# Schematic.net
KiCad netlist of a schematic drawn in EAGLE
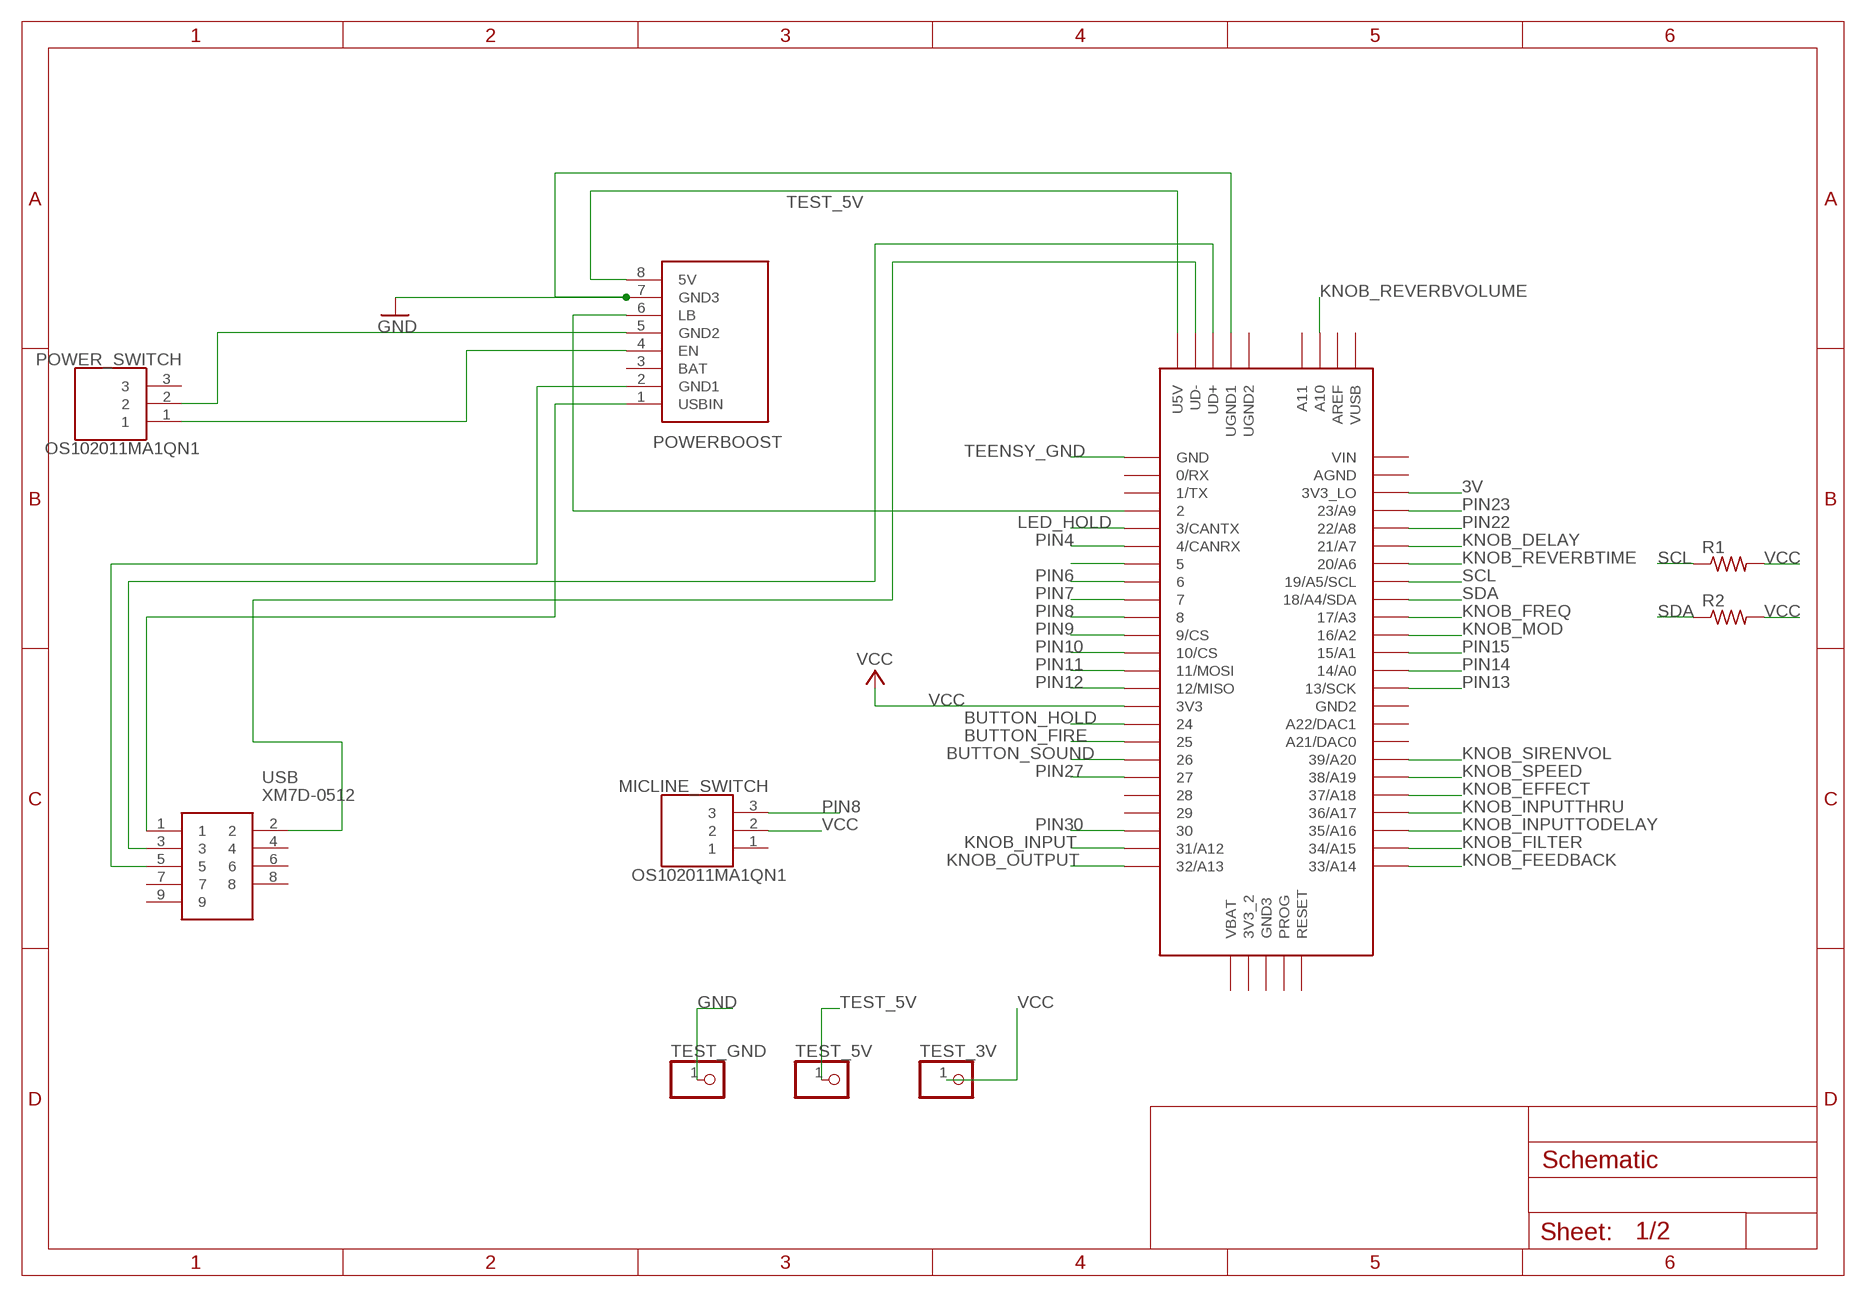
[diagram p0: schematic, sheet 1, part 1 of 2]
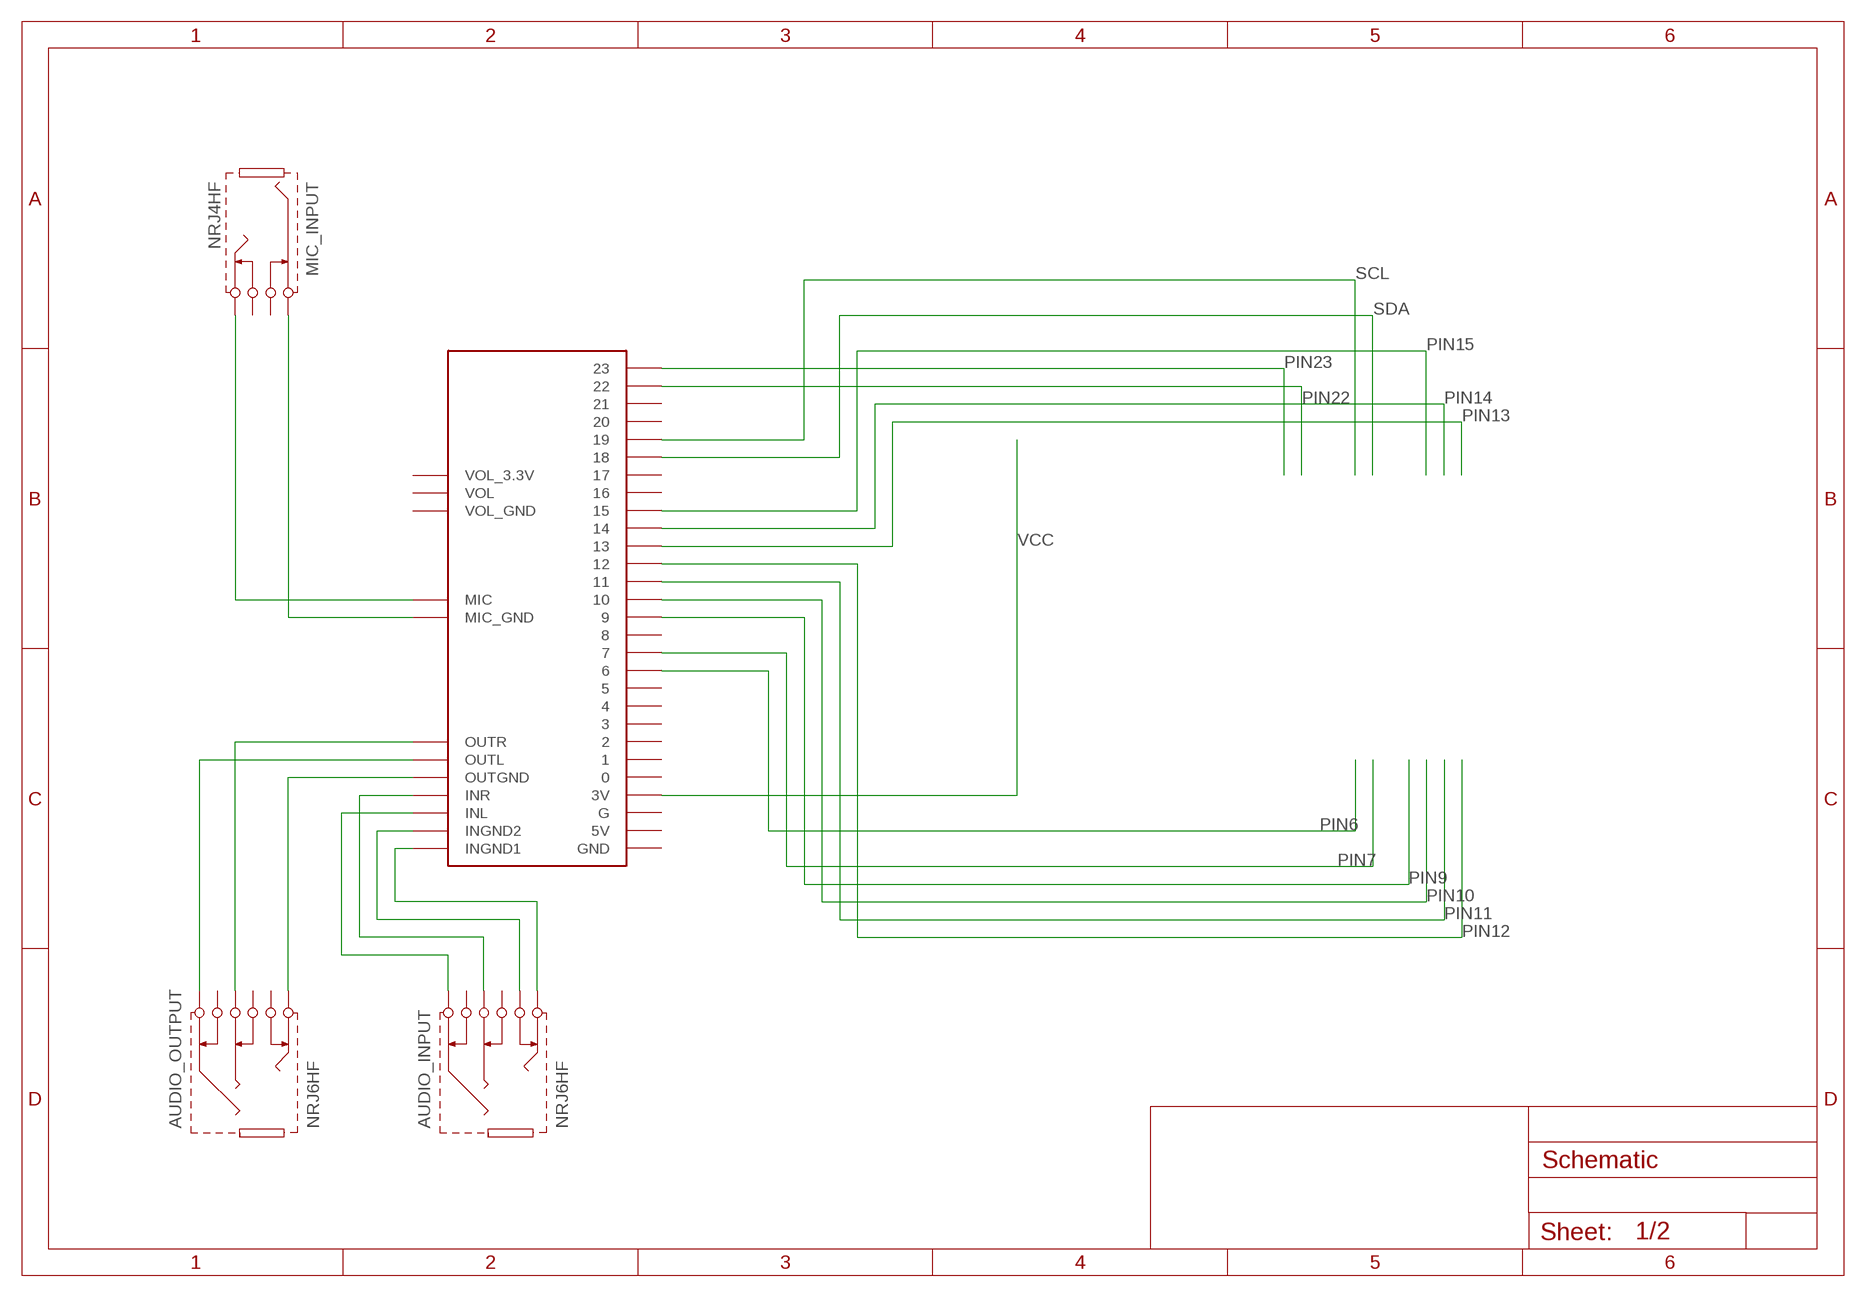
[diagram p1: schematic, sheet 1, part 2 of 2]
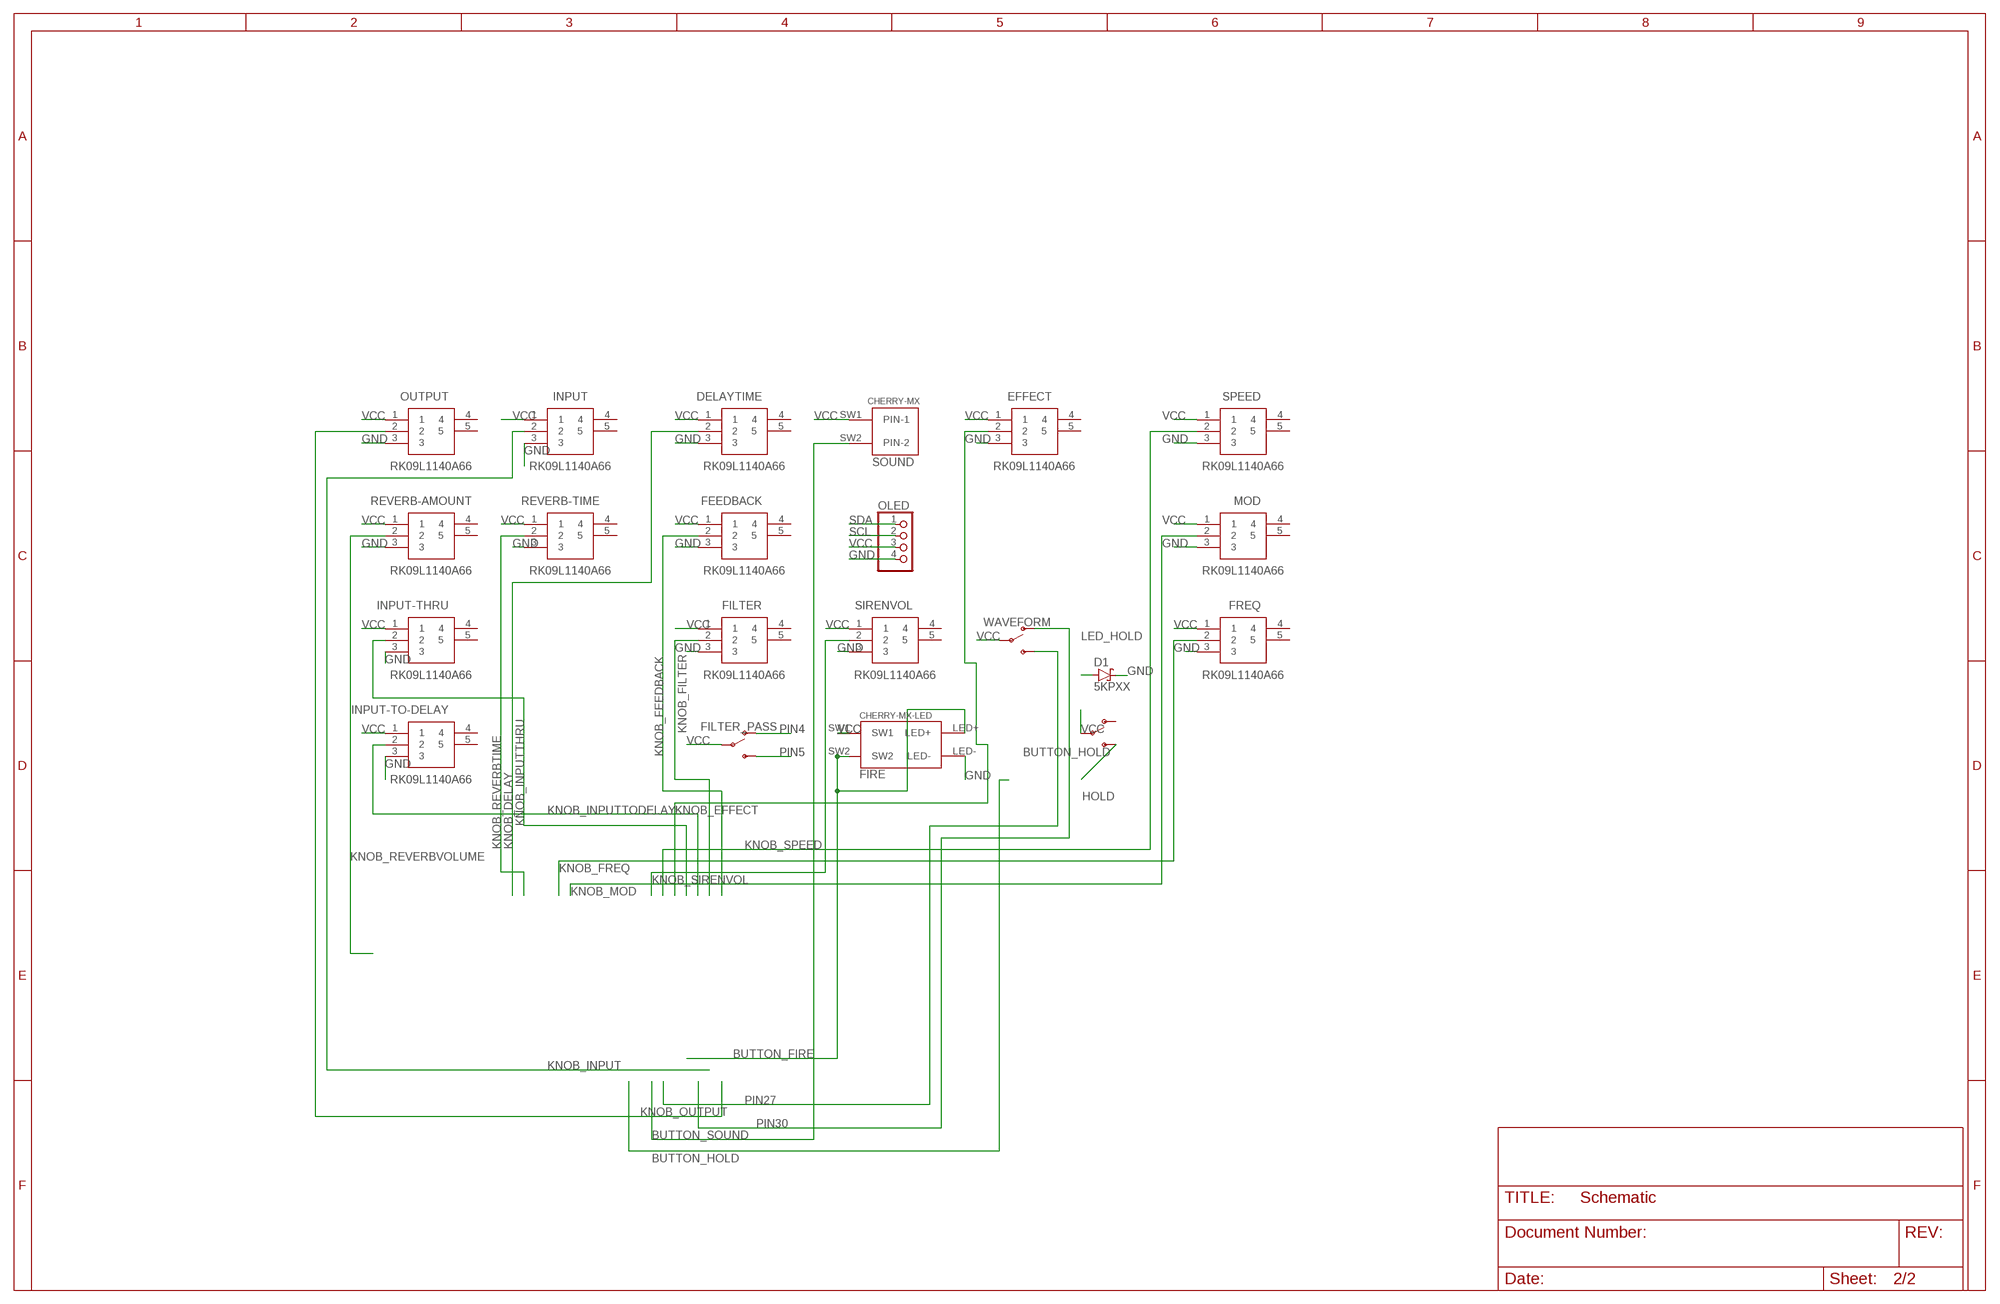
[diagram p2: schematic, sheet 2]

(export (version "E")
  (design (tool "Eeschema 10.0.6"))
  (components
    (comp (ref "D1")
      (value "5KPXX")
      (footprint "eagle-import:P6T15")
      (libsource (lib "eagle-import") (part "5KPXX"))
    )
    (comp (ref "DELAYTIME")
      (value "RK09L1140A66")
      (footprint "eagle-import:RK09L1140A66")
      (fields (field (name "MOUSER_PART_NUMBER") "688-RK09L1140A66"))
      (libsource (lib "eagle-import") (part "RK09L1140A66"))
    )
    (comp (ref "EFFECT")
      (value "RK09L1140A66")
      (footprint "eagle-import:RK09L1140A66")
      (fields (field (name "MOUSER_PART_NUMBER") "688-RK09L1140A66"))
      (libsource (lib "eagle-import") (part "RK09L1140A66"))
    )
    (comp (ref "FEEDBACK")
      (value "RK09L1140A66")
      (footprint "eagle-import:RK09L1140A66")
      (fields (field (name "MOUSER_PART_NUMBER") "688-RK09L1140A66"))
      (libsource (lib "eagle-import") (part "RK09L1140A66"))
    )
    (comp (ref "FILTER")
      (value "RK09L1140A66")
      (footprint "eagle-import:RK09L1140A66")
      (fields (field (name "MOUSER_PART_NUMBER") "688-RK09L1140A66"))
      (libsource (lib "eagle-import") (part "RK09L1140A66"))
    )
    (comp (ref "FILTER_PASS")
      (value "SWITCH-SPDT-PTH-11.6X4.0MM-LOCK")
      (footprint "eagle-import:SWITCH_SPDT_PTH_11.6X4.0MM_LOCK")
      (libsource (lib "eagle-import") (part "SWITCH-SPDT-PTH-11.6X4.0MM-LOCK"))
    )
    (comp (ref "FIRE")
      (value "CHERRY-MX-LED")
      (footprint "eagle-import:CHERRY-MX-LED")
      (libsource (lib "eagle-import") (part "CHERRY-MX-LED"))
    )
    (comp (ref "FREQ")
      (value "RK09L1140A66")
      (footprint "eagle-import:RK09L1140A66")
      (fields (field (name "MOUSER_PART_NUMBER") "688-RK09L1140A66"))
      (libsource (lib "eagle-import") (part "RK09L1140A66"))
    )
    (comp (ref "HOLD")
      (value "SWITCH-SPDT-PTH-11.6X4.0MM-LOCK")
      (footprint "eagle-import:SWITCH_SPDT_PTH_11.6X4.0MM_LOCK")
      (libsource (lib "eagle-import") (part "SWITCH-SPDT-PTH-11.6X4.0MM-LOCK"))
    )
    (comp (ref "INPUT")
      (value "RK09L1140A66")
      (footprint "eagle-import:RK09L1140A66")
      (fields (field (name "MOUSER_PART_NUMBER") "688-RK09L1140A66"))
      (libsource (lib "eagle-import") (part "RK09L1140A66"))
    )
    (comp (ref "INPUT-THRU")
      (value "RK09L1140A66")
      (footprint "eagle-import:RK09L1140A66")
      (fields (field (name "MOUSER_PART_NUMBER") "688-RK09L1140A66"))
      (libsource (lib "eagle-import") (part "RK09L1140A66"))
    )
    (comp (ref "INPUT-TO-DELAY")
      (value "RK09L1140A66")
      (footprint "eagle-import:RK09L1140A66")
      (fields (field (name "MOUSER_PART_NUMBER") "688-RK09L1140A66"))
      (libsource (lib "eagle-import") (part "RK09L1140A66"))
    )
    (comp (ref "MOD")
      (value "RK09L1140A66")
      (footprint "eagle-import:RK09L1140A66")
      (fields (field (name "MOUSER_PART_NUMBER") "688-RK09L1140A66"))
      (libsource (lib "eagle-import") (part "RK09L1140A66"))
    )
    (comp (ref "OLED")
      (value "PINHD-1X4")
      (footprint "eagle-import:1X04")
      (libsource (lib "eagle-import") (part "PINHD-1X4"))
    )
    (comp (ref "OUTPUT")
      (value "RK09L1140A66")
      (footprint "eagle-import:RK09L1140A66")
      (fields (field (name "MOUSER_PART_NUMBER") "688-RK09L1140A66"))
      (libsource (lib "eagle-import") (part "RK09L1140A66"))
    )
    (comp (ref "REVERB-AMOUNT")
      (value "RK09L1140A66")
      (footprint "eagle-import:RK09L1140A66")
      (fields (field (name "MOUSER_PART_NUMBER") "688-RK09L1140A66"))
      (libsource (lib "eagle-import") (part "RK09L1140A66"))
    )
    (comp (ref "REVERB-TIME")
      (value "RK09L1140A66")
      (footprint "eagle-import:RK09L1140A66")
      (fields (field (name "MOUSER_PART_NUMBER") "688-RK09L1140A66"))
      (libsource (lib "eagle-import") (part "RK09L1140A66"))
    )
    (comp (ref "SIRENVOL")
      (value "RK09L1140A66")
      (footprint "eagle-import:RK09L1140A66")
      (fields (field (name "MOUSER_PART_NUMBER") "688-RK09L1140A66"))
      (libsource (lib "eagle-import") (part "RK09L1140A66"))
    )
    (comp (ref "SOUND")
      (value "CHERRY-MX")
      (footprint "eagle-import:CHERRY-MX")
      (libsource (lib "eagle-import") (part "CHERRY-MX"))
    )
    (comp (ref "SPEED")
      (value "RK09L1140A66")
      (footprint "eagle-import:RK09L1140A66")
      (fields (field (name "MOUSER_PART_NUMBER") "688-RK09L1140A66"))
      (libsource (lib "eagle-import") (part "RK09L1140A66"))
    )
    (comp (ref "WAVEFORM")
      (value "SWITCH-SPDT-PTH-11.6X4.0MM-LOCK")
      (footprint "eagle-import:SWITCH_SPDT_PTH_11.6X4.0MM_LOCK")
      (libsource (lib "eagle-import") (part "SWITCH-SPDT-PTH-11.6X4.0MM-LOCK"))
    )
    (comp (ref "AUDIO_INPUT")
      (value "NRJ6HF")
      (footprint "eagle-import:NRJ6HF")
      (libsource (lib "eagle-import") (part "NRJ6HF"))
    )
    (comp (ref "AUDIO_OUTPUT")
      (value "NRJ6HF")
      (footprint "eagle-import:NRJ6HF")
      (libsource (lib "eagle-import") (part "NRJ6HF"))
    )
    (comp (ref "MICLINE_SWITCH")
      (value "OS102011MA1QN1")
      (footprint "eagle-import:OS102011MA1QN1")
      (fields
        (field (name "MOUSER_PART_NUMBER") "611-OS102011MA1QN1")
        (field (name "RS_PART_NUMBER") "7874855")
      )
      (libsource (lib "eagle-import") (part "OS102011MA1QN1"))
    )
    (comp (ref "MIC_INPUT")
      (value "NRJ4HF")
      (footprint "eagle-import:NRJ4HF")
      (libsource (lib "eagle-import") (part "NRJ4HF"))
    )
    (comp (ref "POWER_SWITCH")
      (value "OS102011MA1QN1")
      (footprint "eagle-import:OS102011MA1QN1")
      (fields
        (field (name "MOUSER_PART_NUMBER") "611-OS102011MA1QN1")
        (field (name "RS_PART_NUMBER") "7874855")
      )
      (libsource (lib "eagle-import") (part "OS102011MA1QN1"))
    )
    (comp (ref "R1")
      (value "R-US_0207/10")
      (footprint "eagle-import:0207_10")
      (libsource (lib "eagle-import") (part "R-US_0207/10"))
    )
    (comp (ref "R2")
      (value "R-US_0207/10")
      (footprint "eagle-import:0207_10")
      (libsource (lib "eagle-import") (part "R-US_0207/10"))
    )
    (comp (ref "TEENSY")
      (value "TEENSY_3.5/3.6")
      (footprint "eagle-import:TEENSY_3.5_3.6")
      (libsource (lib "eagle-import") (part "TEENSY_3.5/3.6"))
    )
    (comp (ref "TEST_3V")
      (value "PINHD-1X1")
      (footprint "eagle-import:1X01")
      (libsource (lib "eagle-import") (part "PINHD-1X1"))
    )
    (comp (ref "TEST_5V")
      (value "PINHD-1X1")
      (footprint "eagle-import:1X01")
      (libsource (lib "eagle-import") (part "PINHD-1X1"))
    )
    (comp (ref "TEST_GND")
      (value "PINHD-1X1")
      (footprint "eagle-import:1X01")
      (libsource (lib "eagle-import") (part "PINHD-1X1"))
    )
    (comp (ref "U$2")
      (value "POWERBOOST500C")
      (footprint "eagle-import:POWERBOOST500")
      (libsource (lib "eagle-import") (part "POWERBOOST500C"))
    )
    (comp (ref "U$5")
      (value "AUDIOSHIELD")
      (footprint "eagle-import:AUDIOSHIELD")
      (libsource (lib "eagle-import") (part "AUDIOSHIELD"))
    )
    (comp (ref "USB")
      (value "XM7D-0512")
      (footprint "eagle-import:XM7D0512")
      (fields (field (name "MOUSER_PART_NUMBER") "653-XM7D-0512"))
      (libsource (lib "eagle-import") (part "XM7D-0512"))
    )
  )
  (nets
    (net (code "1") (name "3V") (class "Default")
      (node (ref "TEENSY") (pin "3V3_LO") (pinfunction "3V3_LO_3V3_LO") (pintype "bidirectional"))
    )
    (net (code "2") (name "BUTTON_FIRE") (class "Default")
      (node (ref "FIRE") (pin "LED+") (pinfunction "LED+_LED+") (pintype "bidirectional"))
      (node (ref "FIRE") (pin "SW2") (pinfunction "SW2_SW2") (pintype "bidirectional"))
      (node (ref "TEENSY") (pin "25") (pinfunction "25_25") (pintype "bidirectional"))
    )
    (net (code "3") (name "BUTTON_HOLD") (class "Default")
      (node (ref "HOLD") (pin "3") (pinfunction "S_3") (pintype "passive"))
      (node (ref "TEENSY") (pin "24") (pinfunction "24_24") (pintype "bidirectional"))
    )
    (net (code "4") (name "BUTTON_SOUND") (class "Default")
      (node (ref "SOUND") (pin "SW2") (pinfunction "PIN-2_SW2") (pintype "bidirectional"))
      (node (ref "TEENSY") (pin "26") (pinfunction "26_26") (pintype "bidirectional"))
    )
    (net (code "5") (name "GND") (class "Default")
      (node (ref "D1") (pin "C") (pinfunction "C_C") (pintype "passive"))
      (node (ref "DELAYTIME") (pin "3") (pinfunction "3_3") (pintype "bidirectional"))
      (node (ref "EFFECT") (pin "3") (pinfunction "3_3") (pintype "bidirectional"))
      (node (ref "FEEDBACK") (pin "3") (pinfunction "3_3") (pintype "bidirectional"))
      (node (ref "FILTER") (pin "3") (pinfunction "3_3") (pintype "bidirectional"))
      (node (ref "FIRE") (pin "LED-") (pinfunction "LED-_LED-") (pintype "bidirectional"))
      (node (ref "FREQ") (pin "3") (pinfunction "3_3") (pintype "bidirectional"))
      (node (ref "INPUT") (pin "3") (pinfunction "3_3") (pintype "bidirectional"))
      (node (ref "INPUT-THRU") (pin "3") (pinfunction "3_3") (pintype "bidirectional"))
      (node (ref "INPUT-TO-DELAY") (pin "3") (pinfunction "3_3") (pintype "bidirectional"))
      (node (ref "MOD") (pin "3") (pinfunction "3_3") (pintype "bidirectional"))
      (node (ref "OLED") (pin "4") (pinfunction "4_4") (pintype "passive"))
      (node (ref "OUTPUT") (pin "3") (pinfunction "3_3") (pintype "bidirectional"))
      (node (ref "REVERB-AMOUNT") (pin "3") (pinfunction "3_3") (pintype "bidirectional"))
      (node (ref "REVERB-TIME") (pin "3") (pinfunction "3_3") (pintype "bidirectional"))
      (node (ref "SIRENVOL") (pin "3") (pinfunction "3_3") (pintype "bidirectional"))
      (node (ref "SPEED") (pin "3") (pinfunction "3_3") (pintype "bidirectional"))
      (node (ref "TEENSY") (pin "UGND1") (pinfunction "UGND1_UGND1") (pintype "bidirectional"))
      (node (ref "TEST_GND") (pin "1") (pinfunction "1_1") (pintype "passive"))
      (node (ref "U$2") (pin "7") (pinfunction "GND3_7") (pintype "bidirectional"))
    )
    (net (code "6") (name "KNOB_DELAY") (class "Default")
      (node (ref "DELAYTIME") (pin "2") (pinfunction "2_2") (pintype "bidirectional"))
      (node (ref "TEENSY") (pin "21/A7") (pinfunction "21/A7_21/A7") (pintype "bidirectional"))
    )
    (net (code "7") (name "KNOB_EFFECT") (class "Default")
      (node (ref "EFFECT") (pin "2") (pinfunction "2_2") (pintype "bidirectional"))
      (node (ref "TEENSY") (pin "37/A18") (pinfunction "37/A18_37/A18") (pintype "bidirectional"))
    )
    (net (code "8") (name "KNOB_FEEDBACK") (class "Default")
      (node (ref "FEEDBACK") (pin "2") (pinfunction "2_2") (pintype "bidirectional"))
      (node (ref "TEENSY") (pin "33/A14") (pinfunction "33/A14_33/A14") (pintype "bidirectional"))
    )
    (net (code "9") (name "KNOB_FILTER") (class "Default")
      (node (ref "FILTER") (pin "2") (pinfunction "2_2") (pintype "bidirectional"))
      (node (ref "TEENSY") (pin "34/A15") (pinfunction "34/A15_34/A15") (pintype "bidirectional"))
    )
    (net (code "10") (name "KNOB_FREQ") (class "Default")
      (node (ref "FREQ") (pin "2") (pinfunction "2_2") (pintype "bidirectional"))
      (node (ref "TEENSY") (pin "17/A3") (pinfunction "17/A3_17/A3") (pintype "bidirectional"))
    )
    (net (code "11") (name "KNOB_INPUT") (class "Default")
      (node (ref "INPUT") (pin "2") (pinfunction "2_2") (pintype "bidirectional"))
      (node (ref "TEENSY") (pin "31/A12") (pinfunction "31/A12_31/A12") (pintype "bidirectional"))
    )
    (net (code "12") (name "KNOB_INPUTTHRU") (class "Default")
      (node (ref "INPUT-THRU") (pin "2") (pinfunction "2_2") (pintype "bidirectional"))
      (node (ref "TEENSY") (pin "36/A17") (pinfunction "36/A17_36/A17") (pintype "bidirectional"))
    )
    (net (code "13") (name "KNOB_INPUTTODELAY") (class "Default")
      (node (ref "INPUT-TO-DELAY") (pin "2") (pinfunction "2_2") (pintype "bidirectional"))
      (node (ref "TEENSY") (pin "35/A16") (pinfunction "35/A16_35/A16") (pintype "bidirectional"))
    )
    (net (code "14") (name "KNOB_MOD") (class "Default")
      (node (ref "MOD") (pin "2") (pinfunction "2_2") (pintype "bidirectional"))
      (node (ref "TEENSY") (pin "16/A2") (pinfunction "16/A2_16/A2") (pintype "bidirectional"))
    )
    (net (code "15") (name "KNOB_OUTPUT") (class "Default")
      (node (ref "OUTPUT") (pin "2") (pinfunction "2_2") (pintype "bidirectional"))
      (node (ref "TEENSY") (pin "32/A13") (pinfunction "32/A13_32/A13") (pintype "bidirectional"))
    )
    (net (code "16") (name "KNOB_REVERBTIME") (class "Default")
      (node (ref "REVERB-TIME") (pin "2") (pinfunction "2_2") (pintype "bidirectional"))
      (node (ref "TEENSY") (pin "20/A6") (pinfunction "20/A6_20/A6") (pintype "bidirectional"))
    )
    (net (code "17") (name "KNOB_REVERBVOLUME") (class "Default")
      (node (ref "REVERB-AMOUNT") (pin "2") (pinfunction "2_2") (pintype "bidirectional"))
      (node (ref "TEENSY") (pin "A10") (pinfunction "A10_A10") (pintype "bidirectional"))
    )
    (net (code "18") (name "KNOB_SIRENVOL") (class "Default")
      (node (ref "SIRENVOL") (pin "2") (pinfunction "2_2") (pintype "bidirectional"))
      (node (ref "TEENSY") (pin "39/A20") (pinfunction "39/A20_39/A20") (pintype "bidirectional"))
    )
    (net (code "19") (name "KNOB_SPEED") (class "Default")
      (node (ref "SPEED") (pin "2") (pinfunction "2_2") (pintype "bidirectional"))
      (node (ref "TEENSY") (pin "38/A19") (pinfunction "38/A19_38/A19") (pintype "bidirectional"))
    )
    (net (code "20") (name "LED_HOLD") (class "Default")
      (node (ref "D1") (pin "A") (pinfunction "A_A") (pintype "passive"))
      (node (ref "TEENSY") (pin "3/CANTX") (pinfunction "3/CANTX_3/CANTX") (pintype "bidirectional"))
    )
    (net (code "21") (name "Net-(AUDIO_INPUT-PadRING)") (class "Default")
      (node (ref "AUDIO_INPUT") (pin "RING") (pinfunction "RING_RING") (pintype "passive"))
      (node (ref "U$5") (pin "INR") (pinfunction "INR_INR") (pintype "input"))
    )
    (net (code "22") (name "Net-(AUDIO_INPUT-PadSLEEVE)") (class "Default")
      (node (ref "AUDIO_INPUT") (pin "SLEEVE") (pinfunction "SLEEVE_SLEEVE") (pintype "passive"))
      (node (ref "U$5") (pin "INL") (pinfunction "INL_INL") (pintype "input"))
    )
    (net (code "23") (name "Net-(AUDIO_INPUT-PadTIP)") (class "Default")
      (node (ref "AUDIO_INPUT") (pin "TIP") (pinfunction "TIP_TIP") (pintype "passive"))
      (node (ref "U$5") (pin "INGND1") (pinfunction "INGND1_INGND1") (pintype "bidirectional"))
    )
    (net (code "24") (name "Net-(AUDIO_INPUT-PadTIP-S)") (class "Default")
      (node (ref "AUDIO_INPUT") (pin "TIP-S") (pinfunction "TIP-S_TIP-S") (pintype "passive"))
      (node (ref "U$5") (pin "INGND2") (pinfunction "INGND2_INGND2") (pintype "bidirectional"))
    )
    (net (code "25") (name "Net-(AUDIO_OUTPUT-PadRING)") (class "Default")
      (node (ref "AUDIO_OUTPUT") (pin "RING") (pinfunction "RING_RING") (pintype "passive"))
      (node (ref "U$5") (pin "OUTR") (pinfunction "OUTR_OUTR") (pintype "output"))
    )
    (net (code "26") (name "Net-(AUDIO_OUTPUT-PadSLEEVE)") (class "Default")
      (node (ref "AUDIO_OUTPUT") (pin "SLEEVE") (pinfunction "SLEEVE_SLEEVE") (pintype "passive"))
      (node (ref "U$5") (pin "OUTL") (pinfunction "OUTL_OUTL") (pintype "output"))
    )
    (net (code "27") (name "Net-(AUDIO_OUTPUT-PadTIP)") (class "Default")
      (node (ref "AUDIO_OUTPUT") (pin "TIP") (pinfunction "TIP_TIP") (pintype "passive"))
      (node (ref "U$5") (pin "OUTGND") (pinfunction "OUTGND_OUTGND") (pintype "bidirectional"))
    )
    (net (code "28") (name "Net-(MIC_INPUT-PadTIP)") (class "Default")
      (node (ref "MIC_INPUT") (pin "TIP") (pinfunction "TIP_TIP") (pintype "passive"))
      (node (ref "U$5") (pin "MIC") (pinfunction "MIC_MIC") (pintype "input"))
    )
    (net (code "29") (name "Net-(TEENSY-PadUD+)") (class "Default")
      (node (ref "TEENSY") (pin "UD+") (pinfunction "UD+_UD+") (pintype "bidirectional"))
      (node (ref "USB") (pin "3") (pinfunction "3_3") (pintype "bidirectional"))
    )
    (net (code "30") (name "Net-(TEENSY-PadUD-)") (class "Default")
      (node (ref "TEENSY") (pin "UD-") (pinfunction "UD-_UD-") (pintype "bidirectional"))
      (node (ref "USB") (pin "2") (pinfunction "2_2") (pintype "bidirectional"))
    )
    (net (code "31") (name "Net-(U$2-EN)") (class "Default")
      (node (ref "POWER_SWITCH") (pin "1") (pinfunction "1_1") (pintype "bidirectional"))
      (node (ref "U$2") (pin "4") (pinfunction "EN_4") (pintype "bidirectional"))
    )
    (net (code "32") (name "Net-(U$2-GND1)") (class "Default")
      (node (ref "U$2") (pin "2") (pinfunction "GND1_2") (pintype "bidirectional"))
      (node (ref "USB") (pin "5") (pinfunction "5_5") (pintype "bidirectional"))
    )
    (net (code "33") (name "Net-(U$2-GND2)") (class "Default")
      (node (ref "POWER_SWITCH") (pin "2") (pinfunction "2_2") (pintype "bidirectional"))
      (node (ref "U$2") (pin "5") (pinfunction "GND2_5") (pintype "bidirectional"))
    )
    (net (code "34") (name "Net-(U$2-LB)") (class "Default")
      (node (ref "TEENSY") (pin "2") (pinfunction "2_2") (pintype "bidirectional"))
      (node (ref "U$2") (pin "6") (pinfunction "LB_6") (pintype "bidirectional"))
    )
    (net (code "35") (name "Net-(U$2-USBIN)") (class "Default")
      (node (ref "U$2") (pin "1") (pinfunction "USBIN_1") (pintype "bidirectional"))
      (node (ref "USB") (pin "1") (pinfunction "1_1") (pintype "bidirectional"))
    )
    (net (code "36") (name "Net-(U$5-MIC_GND)") (class "Default")
      (node (ref "MIC_INPUT") (pin "SLEEVE") (pinfunction "SLEEVE_SLEEVE") (pintype "passive"))
      (node (ref "U$5") (pin "GND_MIC") (pinfunction "MIC_GND_GND_MIC") (pintype "bidirectional"))
    )
    (net (code "37") (name "PIN4") (class "Default")
      (node (ref "FILTER_PASS") (pin "1") (pinfunction "O_1") (pintype "passive"))
      (node (ref "TEENSY") (pin "4/CANRX") (pinfunction "4/CANRX_4/CANRX") (pintype "bidirectional"))
    )
    (net (code "38") (name "PIN5") (class "Default")
      (node (ref "FILTER_PASS") (pin "3") (pinfunction "S_3") (pintype "passive"))
      (node (ref "TEENSY") (pin "5") (pinfunction "5_5") (pintype "bidirectional"))
    )
    (net (code "39") (name "PIN6") (class "Default")
      (node (ref "TEENSY") (pin "6") (pinfunction "6_6") (pintype "bidirectional"))
      (node (ref "U$5") (pin "6") (pinfunction "6_6") (pintype "bidirectional"))
    )
    (net (code "40") (name "PIN7") (class "Default")
      (node (ref "TEENSY") (pin "7") (pinfunction "7_7") (pintype "bidirectional"))
      (node (ref "U$5") (pin "7") (pinfunction "7_7") (pintype "bidirectional"))
    )
    (net (code "41") (name "PIN8") (class "Default")
      (node (ref "MICLINE_SWITCH") (pin "3") (pinfunction "3_3") (pintype "bidirectional"))
      (node (ref "TEENSY") (pin "8") (pinfunction "8_8") (pintype "bidirectional"))
    )
    (net (code "42") (name "PIN9") (class "Default")
      (node (ref "TEENSY") (pin "9/CS") (pinfunction "9/CS_9/CS") (pintype "bidirectional"))
      (node (ref "U$5") (pin "9") (pinfunction "9_9") (pintype "bidirectional"))
    )
    (net (code "43") (name "PIN10") (class "Default")
      (node (ref "TEENSY") (pin "10/CS") (pinfunction "10/CS_10/CS") (pintype "bidirectional"))
      (node (ref "U$5") (pin "10") (pinfunction "10_10") (pintype "bidirectional"))
    )
    (net (code "44") (name "PIN11") (class "Default")
      (node (ref "TEENSY") (pin "11/MOSI") (pinfunction "11/MOSI_11/MOSI") (pintype "bidirectional"))
      (node (ref "U$5") (pin "11") (pinfunction "11_11") (pintype "bidirectional"))
    )
    (net (code "45") (name "PIN12") (class "Default")
      (node (ref "TEENSY") (pin "12/MISO") (pinfunction "12/MISO_12/MISO") (pintype "bidirectional"))
      (node (ref "U$5") (pin "12") (pinfunction "12_12") (pintype "bidirectional"))
    )
    (net (code "46") (name "PIN13") (class "Default")
      (node (ref "TEENSY") (pin "13/SCK") (pinfunction "13/SCK_13/SCK") (pintype "bidirectional"))
      (node (ref "U$5") (pin "13") (pinfunction "13_13") (pintype "bidirectional"))
    )
    (net (code "47") (name "PIN14") (class "Default")
      (node (ref "TEENSY") (pin "14/A0") (pinfunction "14/A0_14/A0") (pintype "bidirectional"))
      (node (ref "U$5") (pin "14") (pinfunction "14_14") (pintype "bidirectional"))
    )
    (net (code "48") (name "PIN15") (class "Default")
      (node (ref "TEENSY") (pin "15/A1") (pinfunction "15/A1_15/A1") (pintype "bidirectional"))
      (node (ref "U$5") (pin "15") (pinfunction "15_15") (pintype "bidirectional"))
    )
    (net (code "49") (name "PIN22") (class "Default")
      (node (ref "TEENSY") (pin "22/A8") (pinfunction "22/A8_22/A8") (pintype "bidirectional"))
      (node (ref "U$5") (pin "22") (pinfunction "22_22") (pintype "bidirectional"))
    )
    (net (code "50") (name "PIN23") (class "Default")
      (node (ref "TEENSY") (pin "23/A9") (pinfunction "23/A9_23/A9") (pintype "bidirectional"))
      (node (ref "U$5") (pin "23") (pinfunction "23_23") (pintype "bidirectional"))
    )
    (net (code "51") (name "PIN27") (class "Default")
      (node (ref "TEENSY") (pin "27") (pinfunction "27_27") (pintype "bidirectional"))
      (node (ref "WAVEFORM") (pin "3") (pinfunction "S_3") (pintype "passive"))
    )
    (net (code "52") (name "PIN30") (class "Default")
      (node (ref "TEENSY") (pin "30") (pinfunction "30_30") (pintype "bidirectional"))
      (node (ref "WAVEFORM") (pin "1") (pinfunction "O_1") (pintype "passive"))
    )
    (net (code "53") (name "SCL") (class "Default")
      (node (ref "OLED") (pin "2") (pinfunction "2_2") (pintype "passive"))
      (node (ref "R1") (pin "1") (pinfunction "1_1") (pintype "passive"))
      (node (ref "TEENSY") (pin "19/A5/SCL") (pinfunction "19/A5/SCL_19/A5/SCL") (pintype "bidirectional"))
      (node (ref "U$5") (pin "19") (pinfunction "19_19") (pintype "bidirectional"))
    )
    (net (code "54") (name "SDA") (class "Default")
      (node (ref "OLED") (pin "1") (pinfunction "1_1") (pintype "passive"))
      (node (ref "R2") (pin "1") (pinfunction "1_1") (pintype "passive"))
      (node (ref "TEENSY") (pin "18/A4/SDA") (pinfunction "18/A4/SDA_18/A4/SDA") (pintype "bidirectional"))
      (node (ref "U$5") (pin "18") (pinfunction "18_18") (pintype "bidirectional"))
    )
    (net (code "55") (name "TEENSY_GND") (class "Default")
      (node (ref "TEENSY") (pin "GND") (pinfunction "GND_GND") (pintype "bidirectional"))
    )
    (net (code "56") (name "TEST_5V") (class "Default")
      (node (ref "TEENSY") (pin "U5V") (pinfunction "U5V_U5V") (pintype "bidirectional"))
      (node (ref "TEST_5V") (pin "1") (pinfunction "1_1") (pintype "passive"))
      (node (ref "U$2") (pin "8") (pinfunction "5V_8") (pintype "bidirectional"))
    )
    (net (code "57") (name "VCC") (class "Default")
      (node (ref "DELAYTIME") (pin "1") (pinfunction "1_1") (pintype "bidirectional"))
      (node (ref "EFFECT") (pin "1") (pinfunction "1_1") (pintype "bidirectional"))
      (node (ref "FEEDBACK") (pin "1") (pinfunction "1_1") (pintype "bidirectional"))
      (node (ref "FILTER") (pin "1") (pinfunction "1_1") (pintype "bidirectional"))
      (node (ref "FILTER_PASS") (pin "2") (pinfunction "P_2") (pintype "passive"))
      (node (ref "FIRE") (pin "SW1") (pinfunction "SW1_SW1") (pintype "bidirectional"))
      (node (ref "FREQ") (pin "1") (pinfunction "1_1") (pintype "bidirectional"))
      (node (ref "HOLD") (pin "2") (pinfunction "P_2") (pintype "passive"))
      (node (ref "INPUT") (pin "1") (pinfunction "1_1") (pintype "bidirectional"))
      (node (ref "INPUT-THRU") (pin "1") (pinfunction "1_1") (pintype "bidirectional"))
      (node (ref "INPUT-TO-DELAY") (pin "1") (pinfunction "1_1") (pintype "bidirectional"))
      (node (ref "MICLINE_SWITCH") (pin "2") (pinfunction "2_2") (pintype "bidirectional"))
      (node (ref "MOD") (pin "1") (pinfunction "1_1") (pintype "bidirectional"))
      (node (ref "OLED") (pin "3") (pinfunction "3_3") (pintype "passive"))
      (node (ref "OUTPUT") (pin "1") (pinfunction "1_1") (pintype "bidirectional"))
      (node (ref "R1") (pin "2") (pinfunction "2_2") (pintype "passive"))
      (node (ref "R2") (pin "2") (pinfunction "2_2") (pintype "passive"))
      (node (ref "REVERB-AMOUNT") (pin "1") (pinfunction "1_1") (pintype "bidirectional"))
      (node (ref "REVERB-TIME") (pin "1") (pinfunction "1_1") (pintype "bidirectional"))
      (node (ref "SIRENVOL") (pin "1") (pinfunction "1_1") (pintype "bidirectional"))
      (node (ref "SOUND") (pin "SW1") (pinfunction "PIN-1_SW1") (pintype "bidirectional"))
      (node (ref "SPEED") (pin "1") (pinfunction "1_1") (pintype "bidirectional"))
      (node (ref "TEENSY") (pin "3V3") (pinfunction "3V3_3V3") (pintype "bidirectional"))
      (node (ref "TEST_3V") (pin "1") (pinfunction "1_1") (pintype "passive"))
      (node (ref "U$5") (pin "3V") (pinfunction "3V_3V") (pintype "bidirectional"))
      (node (ref "WAVEFORM") (pin "2") (pinfunction "P_2") (pintype "passive"))
    )
    (net (code "58") (name "unconnected-(AUDIO_INPUT-PadRING-S)") (class "Default")
      (node (ref "AUDIO_INPUT") (pin "RING-S") (pinfunction "RING-S_RING-S") (pintype "passive"))
    )
    (net (code "59") (name "unconnected-(AUDIO_INPUT-PadSLEEVE-S)") (class "Default")
      (node (ref "AUDIO_INPUT") (pin "SLEEVE-S") (pinfunction "SLEEVE-S_SLEEVE-S") (pintype "passive"))
    )
    (net (code "60") (name "unconnected-(AUDIO_OUTPUT-PadRING-S)") (class "Default")
      (node (ref "AUDIO_OUTPUT") (pin "RING-S") (pinfunction "RING-S_RING-S") (pintype "passive"))
    )
    (net (code "61") (name "unconnected-(AUDIO_OUTPUT-PadSLEEVE-S)") (class "Default")
      (node (ref "AUDIO_OUTPUT") (pin "SLEEVE-S") (pinfunction "SLEEVE-S_SLEEVE-S") (pintype "passive"))
    )
    (net (code "62") (name "unconnected-(AUDIO_OUTPUT-PadTIP-S)") (class "Default")
      (node (ref "AUDIO_OUTPUT") (pin "TIP-S") (pinfunction "TIP-S_TIP-S") (pintype "passive"))
    )
    (net (code "63") (name "unconnected-(DELAYTIME-Pad4)") (class "Default")
      (node (ref "DELAYTIME") (pin "4") (pinfunction "4_4") (pintype "bidirectional"))
    )
    (net (code "64") (name "unconnected-(DELAYTIME-Pad5)") (class "Default")
      (node (ref "DELAYTIME") (pin "5") (pinfunction "5_5") (pintype "bidirectional"))
    )
    (net (code "65") (name "unconnected-(EFFECT-Pad4)") (class "Default")
      (node (ref "EFFECT") (pin "4") (pinfunction "4_4") (pintype "bidirectional"))
    )
    (net (code "66") (name "unconnected-(EFFECT-Pad5)") (class "Default")
      (node (ref "EFFECT") (pin "5") (pinfunction "5_5") (pintype "bidirectional"))
    )
    (net (code "67") (name "unconnected-(FEEDBACK-Pad4)") (class "Default")
      (node (ref "FEEDBACK") (pin "4") (pinfunction "4_4") (pintype "bidirectional"))
    )
    (net (code "68") (name "unconnected-(FEEDBACK-Pad5)") (class "Default")
      (node (ref "FEEDBACK") (pin "5") (pinfunction "5_5") (pintype "bidirectional"))
    )
    (net (code "69") (name "unconnected-(FILTER-Pad4)") (class "Default")
      (node (ref "FILTER") (pin "4") (pinfunction "4_4") (pintype "bidirectional"))
    )
    (net (code "70") (name "unconnected-(FILTER-Pad5)") (class "Default")
      (node (ref "FILTER") (pin "5") (pinfunction "5_5") (pintype "bidirectional"))
    )
    (net (code "71") (name "unconnected-(FREQ-Pad4)") (class "Default")
      (node (ref "FREQ") (pin "4") (pinfunction "4_4") (pintype "bidirectional"))
    )
    (net (code "72") (name "unconnected-(FREQ-Pad5)") (class "Default")
      (node (ref "FREQ") (pin "5") (pinfunction "5_5") (pintype "bidirectional"))
    )
    (net (code "73") (name "unconnected-(HOLD-O-Pad1)") (class "Default")
      (node (ref "HOLD") (pin "1") (pinfunction "O_1") (pintype "passive"))
    )
    (net (code "74") (name "unconnected-(INPUT-Pad4)") (class "Default")
      (node (ref "INPUT") (pin "4") (pinfunction "4_4") (pintype "bidirectional"))
    )
    (net (code "75") (name "unconnected-(INPUT-Pad5)") (class "Default")
      (node (ref "INPUT") (pin "5") (pinfunction "5_5") (pintype "bidirectional"))
    )
    (net (code "76") (name "unconnected-(INPUT-THRU-Pad4)") (class "Default")
      (node (ref "INPUT-THRU") (pin "4") (pinfunction "4_4") (pintype "bidirectional"))
    )
    (net (code "77") (name "unconnected-(INPUT-THRU-Pad5)") (class "Default")
      (node (ref "INPUT-THRU") (pin "5") (pinfunction "5_5") (pintype "bidirectional"))
    )
    (net (code "78") (name "unconnected-(INPUT-TO-DELAY-Pad4)") (class "Default")
      (node (ref "INPUT-TO-DELAY") (pin "4") (pinfunction "4_4") (pintype "bidirectional"))
    )
    (net (code "79") (name "unconnected-(INPUT-TO-DELAY-Pad5)") (class "Default")
      (node (ref "INPUT-TO-DELAY") (pin "5") (pinfunction "5_5") (pintype "bidirectional"))
    )
    (net (code "80") (name "unconnected-(MICLINE_SWITCH-Pad1)") (class "Default")
      (node (ref "MICLINE_SWITCH") (pin "1") (pinfunction "1_1") (pintype "bidirectional"))
    )
    (net (code "81") (name "unconnected-(MIC_INPUT-PadSLEEVE-S)") (class "Default")
      (node (ref "MIC_INPUT") (pin "SLEEVE-S") (pinfunction "SLEEVE-S_SLEEVE-S") (pintype "passive"))
    )
    (net (code "82") (name "unconnected-(MIC_INPUT-PadTIP-S)") (class "Default")
      (node (ref "MIC_INPUT") (pin "TIP-S") (pinfunction "TIP-S_TIP-S") (pintype "passive"))
    )
    (net (code "83") (name "unconnected-(MOD-Pad4)") (class "Default")
      (node (ref "MOD") (pin "4") (pinfunction "4_4") (pintype "bidirectional"))
    )
    (net (code "84") (name "unconnected-(MOD-Pad5)") (class "Default")
      (node (ref "MOD") (pin "5") (pinfunction "5_5") (pintype "bidirectional"))
    )
    (net (code "85") (name "unconnected-(OUTPUT-Pad4)") (class "Default")
      (node (ref "OUTPUT") (pin "4") (pinfunction "4_4") (pintype "bidirectional"))
    )
    (net (code "86") (name "unconnected-(OUTPUT-Pad5)") (class "Default")
      (node (ref "OUTPUT") (pin "5") (pinfunction "5_5") (pintype "bidirectional"))
    )
    (net (code "87") (name "unconnected-(POWER_SWITCH-Pad3)") (class "Default")
      (node (ref "POWER_SWITCH") (pin "3") (pinfunction "3_3") (pintype "bidirectional"))
    )
    (net (code "88") (name "unconnected-(REVERB-AMOUNT-Pad4)") (class "Default")
      (node (ref "REVERB-AMOUNT") (pin "4") (pinfunction "4_4") (pintype "bidirectional"))
    )
    (net (code "89") (name "unconnected-(REVERB-AMOUNT-Pad5)") (class "Default")
      (node (ref "REVERB-AMOUNT") (pin "5") (pinfunction "5_5") (pintype "bidirectional"))
    )
    (net (code "90") (name "unconnected-(REVERB-TIME-Pad4)") (class "Default")
      (node (ref "REVERB-TIME") (pin "4") (pinfunction "4_4") (pintype "bidirectional"))
    )
    (net (code "91") (name "unconnected-(REVERB-TIME-Pad5)") (class "Default")
      (node (ref "REVERB-TIME") (pin "5") (pinfunction "5_5") (pintype "bidirectional"))
    )
    (net (code "92") (name "unconnected-(SIRENVOL-Pad4)") (class "Default")
      (node (ref "SIRENVOL") (pin "4") (pinfunction "4_4") (pintype "bidirectional"))
    )
    (net (code "93") (name "unconnected-(SIRENVOL-Pad5)") (class "Default")
      (node (ref "SIRENVOL") (pin "5") (pinfunction "5_5") (pintype "bidirectional"))
    )
    (net (code "94") (name "unconnected-(SPEED-Pad4)") (class "Default")
      (node (ref "SPEED") (pin "4") (pinfunction "4_4") (pintype "bidirectional"))
    )
    (net (code "95") (name "unconnected-(SPEED-Pad5)") (class "Default")
      (node (ref "SPEED") (pin "5") (pinfunction "5_5") (pintype "bidirectional"))
    )
    (net (code "96") (name "unconnected-(TEENSY-A21{slash}DAC0-Pad21{slash}DAC0)") (class "Default")
      (node (ref "TEENSY") (pin "21/DAC0") (pinfunction "A21/DAC0_21/DAC0") (pintype "bidirectional"))
    )
    (net (code "97") (name "unconnected-(TEENSY-Pad0{slash}RX)") (class "Default")
      (node (ref "TEENSY") (pin "0/RX") (pinfunction "0/RX_0/RX") (pintype "bidirectional"))
    )
    (net (code "98") (name "unconnected-(TEENSY-Pad1{slash}TX)") (class "Default")
      (node (ref "TEENSY") (pin "1/TX") (pinfunction "1/TX_1/TX") (pintype "bidirectional"))
    )
    (net (code "99") (name "unconnected-(TEENSY-Pad3V3_2)") (class "Default")
      (node (ref "TEENSY") (pin "3V3_2") (pinfunction "3V3_2_3V3_2") (pintype "bidirectional"))
    )
    (net (code "100") (name "unconnected-(TEENSY-Pad28)") (class "Default")
      (node (ref "TEENSY") (pin "28") (pinfunction "28_28") (pintype "bidirectional"))
    )
    (net (code "101") (name "unconnected-(TEENSY-Pad29)") (class "Default")
      (node (ref "TEENSY") (pin "29") (pinfunction "29_29") (pintype "bidirectional"))
    )
    (net (code "102") (name "unconnected-(TEENSY-PadA11)") (class "Default")
      (node (ref "TEENSY") (pin "A11") (pinfunction "A11_A11") (pintype "bidirectional"))
    )
    (net (code "103") (name "unconnected-(TEENSY-PadA22{slash}DAC1)") (class "Default")
      (node (ref "TEENSY") (pin "A22/DAC1") (pinfunction "A22/DAC1_A22/DAC1") (pintype "bidirectional"))
    )
    (net (code "104") (name "unconnected-(TEENSY-PadAGND)") (class "Default")
      (node (ref "TEENSY") (pin "AGND") (pinfunction "AGND_AGND") (pintype "bidirectional"))
    )
    (net (code "105") (name "unconnected-(TEENSY-PadAREF)") (class "Default")
      (node (ref "TEENSY") (pin "AREF") (pinfunction "AREF_AREF") (pintype "bidirectional"))
    )
    (net (code "106") (name "unconnected-(TEENSY-PadGND2)") (class "Default")
      (node (ref "TEENSY") (pin "GND2") (pinfunction "GND2_GND2") (pintype "bidirectional"))
    )
    (net (code "107") (name "unconnected-(TEENSY-PadGND3)") (class "Default")
      (node (ref "TEENSY") (pin "GND3") (pinfunction "GND3_GND3") (pintype "bidirectional"))
    )
    (net (code "108") (name "unconnected-(TEENSY-PadPROG)") (class "Default")
      (node (ref "TEENSY") (pin "PROG") (pinfunction "PROG_PROG") (pintype "bidirectional"))
    )
    (net (code "109") (name "unconnected-(TEENSY-PadRESET)") (class "Default")
      (node (ref "TEENSY") (pin "RESET") (pinfunction "RESET_RESET") (pintype "bidirectional"))
    )
    (net (code "110") (name "unconnected-(TEENSY-PadUGND2)") (class "Default")
      (node (ref "TEENSY") (pin "UGND2") (pinfunction "UGND2_UGND2") (pintype "bidirectional"))
    )
    (net (code "111") (name "unconnected-(TEENSY-PadVBAT)") (class "Default")
      (node (ref "TEENSY") (pin "VBAT") (pinfunction "VBAT_VBAT") (pintype "bidirectional"))
    )
    (net (code "112") (name "unconnected-(TEENSY-PadVIN)") (class "Default")
      (node (ref "TEENSY") (pin "VIN") (pinfunction "VIN_VIN") (pintype "bidirectional"))
    )
    (net (code "113") (name "unconnected-(TEENSY-PadVUSB)") (class "Default")
      (node (ref "TEENSY") (pin "VUSB") (pinfunction "VUSB_VUSB") (pintype "bidirectional"))
    )
    (net (code "114") (name "unconnected-(U$2-BAT-Pad3)") (class "Default")
      (node (ref "U$2") (pin "3") (pinfunction "BAT_3") (pintype "bidirectional"))
    )
    (net (code "115") (name "unconnected-(U$5-Pad0)") (class "Default")
      (node (ref "U$5") (pin "0") (pinfunction "0_0") (pintype "bidirectional"))
    )
    (net (code "116") (name "unconnected-(U$5-Pad1)") (class "Default")
      (node (ref "U$5") (pin "1") (pinfunction "1_1") (pintype "bidirectional"))
    )
    (net (code "117") (name "unconnected-(U$5-Pad2)") (class "Default")
      (node (ref "U$5") (pin "2") (pinfunction "2_2") (pintype "bidirectional"))
    )
    (net (code "118") (name "unconnected-(U$5-Pad3)") (class "Default")
      (node (ref "U$5") (pin "3") (pinfunction "3_3") (pintype "bidirectional"))
    )
    (net (code "119") (name "unconnected-(U$5-Pad4)") (class "Default")
      (node (ref "U$5") (pin "4") (pinfunction "4_4") (pintype "bidirectional"))
    )
    (net (code "120") (name "unconnected-(U$5-Pad5)") (class "Default")
      (node (ref "U$5") (pin "5") (pinfunction "5_5") (pintype "bidirectional"))
    )
    (net (code "121") (name "unconnected-(U$5-Pad5V)") (class "Default")
      (node (ref "U$5") (pin "5V") (pinfunction "5V_5V") (pintype "bidirectional"))
    )
    (net (code "122") (name "unconnected-(U$5-Pad8)") (class "Default")
      (node (ref "U$5") (pin "8") (pinfunction "8_8") (pintype "bidirectional"))
    )
    (net (code "123") (name "unconnected-(U$5-Pad16)") (class "Default")
      (node (ref "U$5") (pin "16") (pinfunction "16_16") (pintype "bidirectional"))
    )
    (net (code "124") (name "unconnected-(U$5-Pad17)") (class "Default")
      (node (ref "U$5") (pin "17") (pinfunction "17_17") (pintype "bidirectional"))
    )
    (net (code "125") (name "unconnected-(U$5-Pad20)") (class "Default")
      (node (ref "U$5") (pin "20") (pinfunction "20_20") (pintype "bidirectional"))
    )
    (net (code "126") (name "unconnected-(U$5-Pad21)") (class "Default")
      (node (ref "U$5") (pin "21") (pinfunction "21_21") (pintype "bidirectional"))
    )
    (net (code "127") (name "unconnected-(U$5-PadG)") (class "Default")
      (node (ref "U$5") (pin "G") (pinfunction "G_G") (pintype "bidirectional"))
    )
    (net (code "128") (name "unconnected-(U$5-PadGND)") (class "Default")
      (node (ref "U$5") (pin "GND") (pinfunction "GND_GND") (pintype "bidirectional"))
    )
    (net (code "129") (name "unconnected-(U$5-PadVOL)") (class "Default")
      (node (ref "U$5") (pin "VOL") (pinfunction "VOL_VOL") (pintype "input"))
    )
    (net (code "130") (name "unconnected-(U$5-PadVOL_3.3V)") (class "Default")
      (node (ref "U$5") (pin "VOL_3.3V") (pinfunction "VOL_3.3V_VOL_3.3V") (pintype "bidirectional"))
    )
    (net (code "131") (name "unconnected-(U$5-PadVOL_GND)") (class "Default")
      (node (ref "U$5") (pin "VOL_GND") (pinfunction "VOL_GND_VOL_GND") (pintype "bidirectional"))
    )
    (net (code "132") (name "unconnected-(USB-Pad4)") (class "Default")
      (node (ref "USB") (pin "4") (pinfunction "4_4") (pintype "bidirectional"))
    )
    (net (code "133") (name "unconnected-(USB-Pad6)") (class "Default")
      (node (ref "USB") (pin "6") (pinfunction "6_6") (pintype "bidirectional"))
    )
    (net (code "134") (name "unconnected-(USB-Pad7)") (class "Default")
      (node (ref "USB") (pin "7") (pinfunction "7_7") (pintype "bidirectional"))
    )
    (net (code "135") (name "unconnected-(USB-Pad8)") (class "Default")
      (node (ref "USB") (pin "8") (pinfunction "8_8") (pintype "bidirectional"))
    )
    (net (code "136") (name "unconnected-(USB-Pad9)") (class "Default")
      (node (ref "USB") (pin "9") (pinfunction "9_9") (pintype "bidirectional"))
    )
  )
)
